# PAC_MiP_POV_v18_10_18_17_new_02.net
KiCad netlist of a schematic drawn in EAGLE
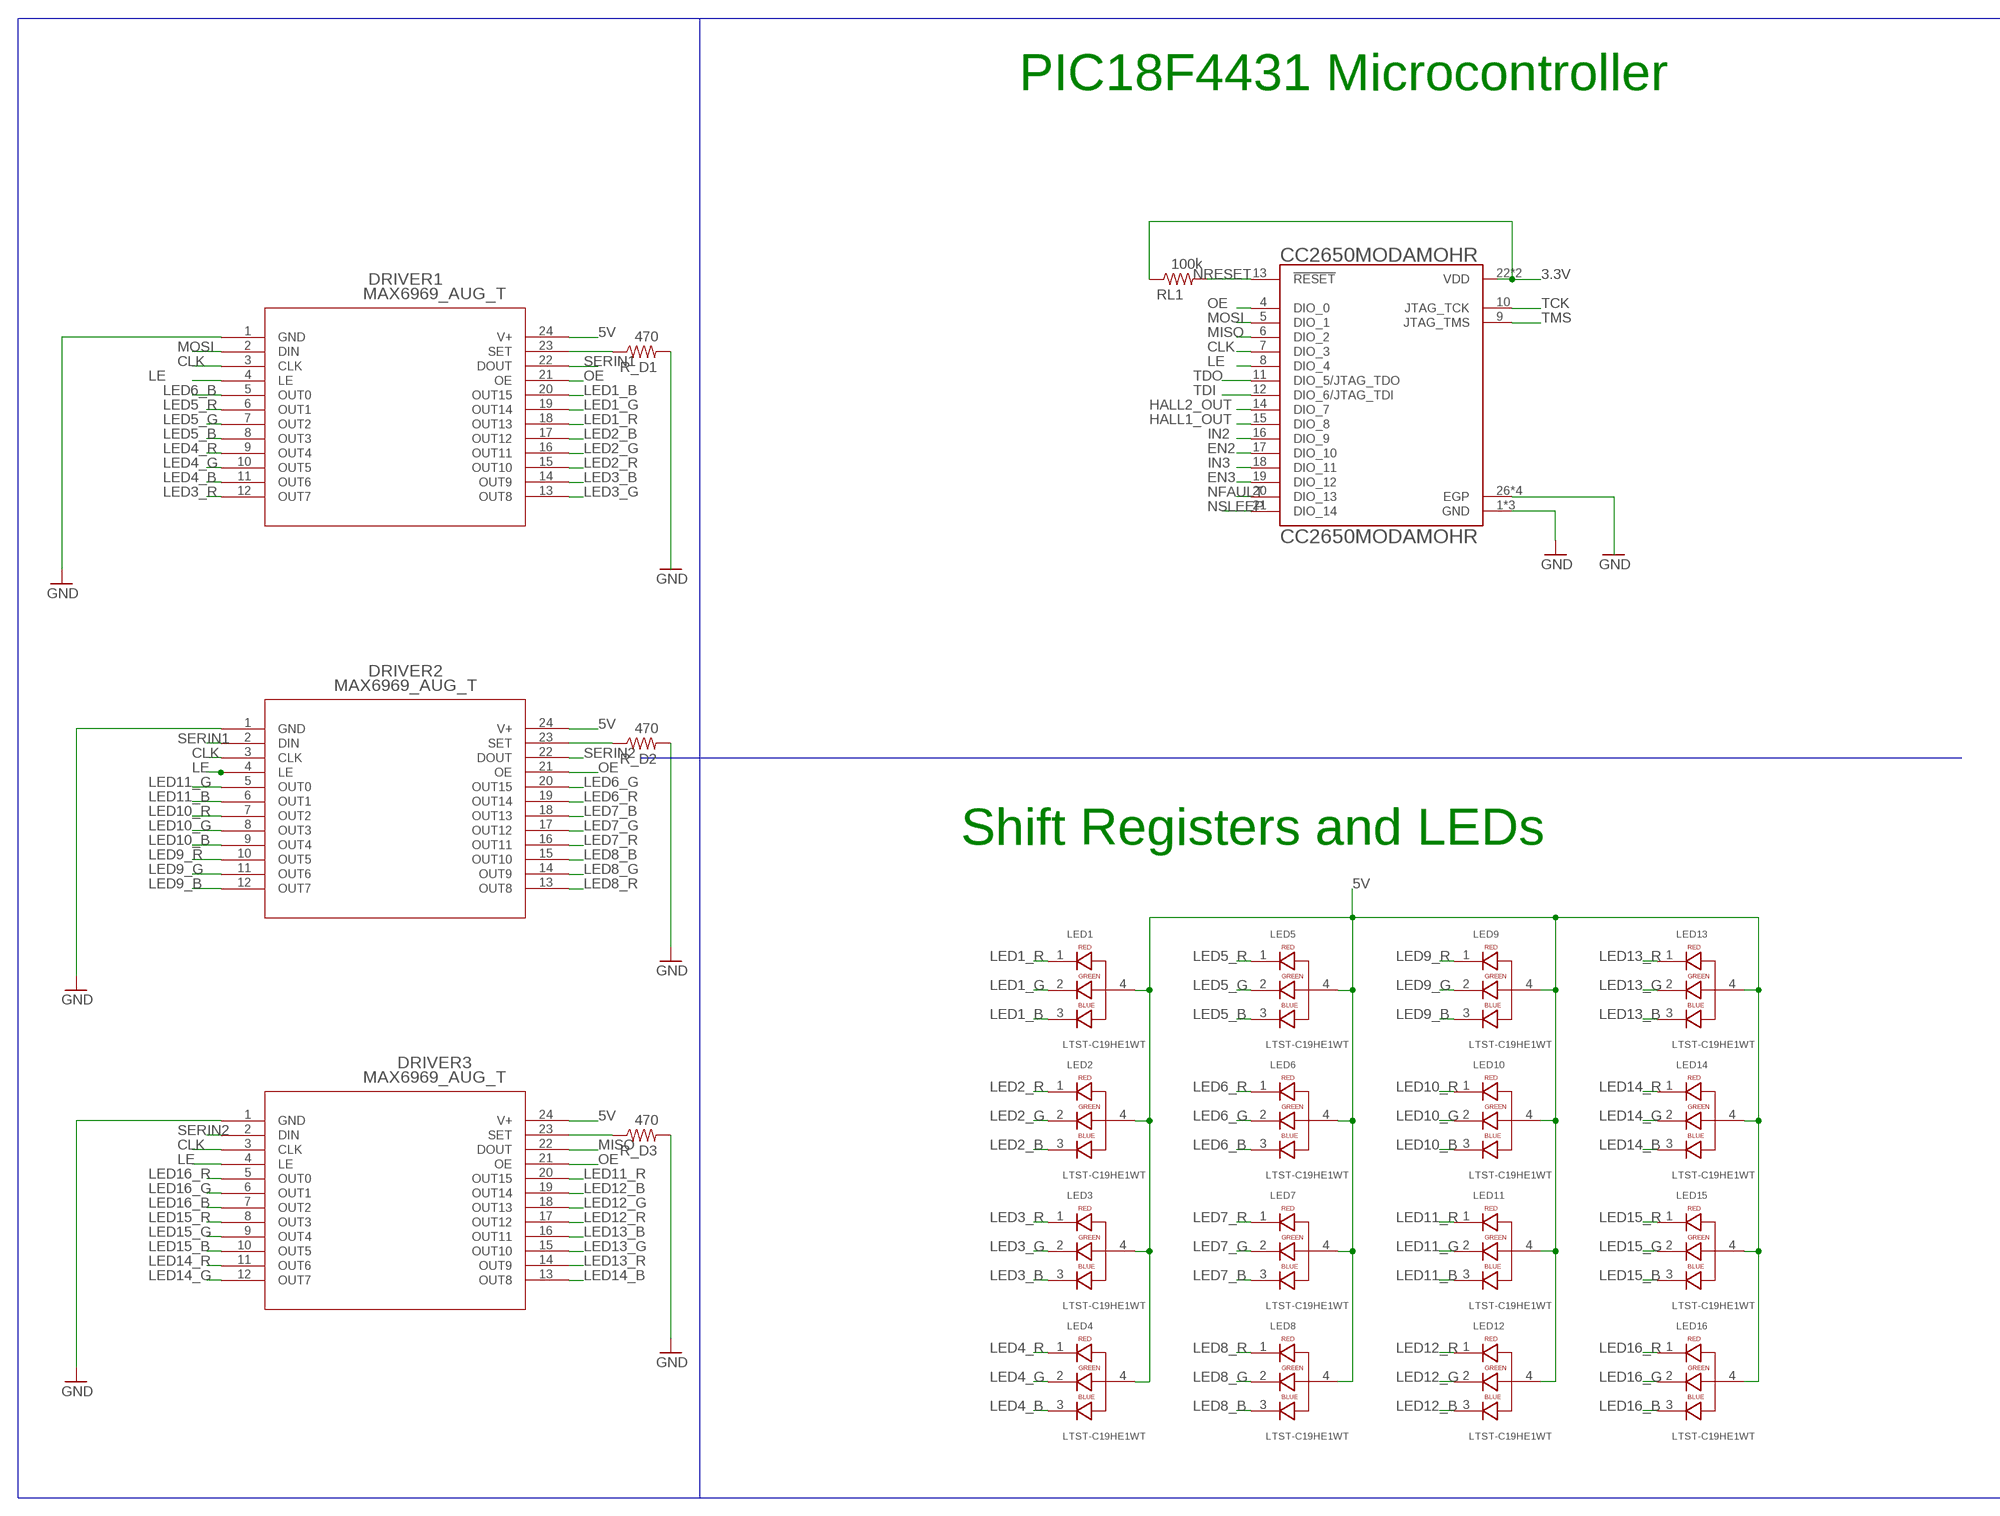
[diagram p0: schematic, sheet 1, part 1 of 2]
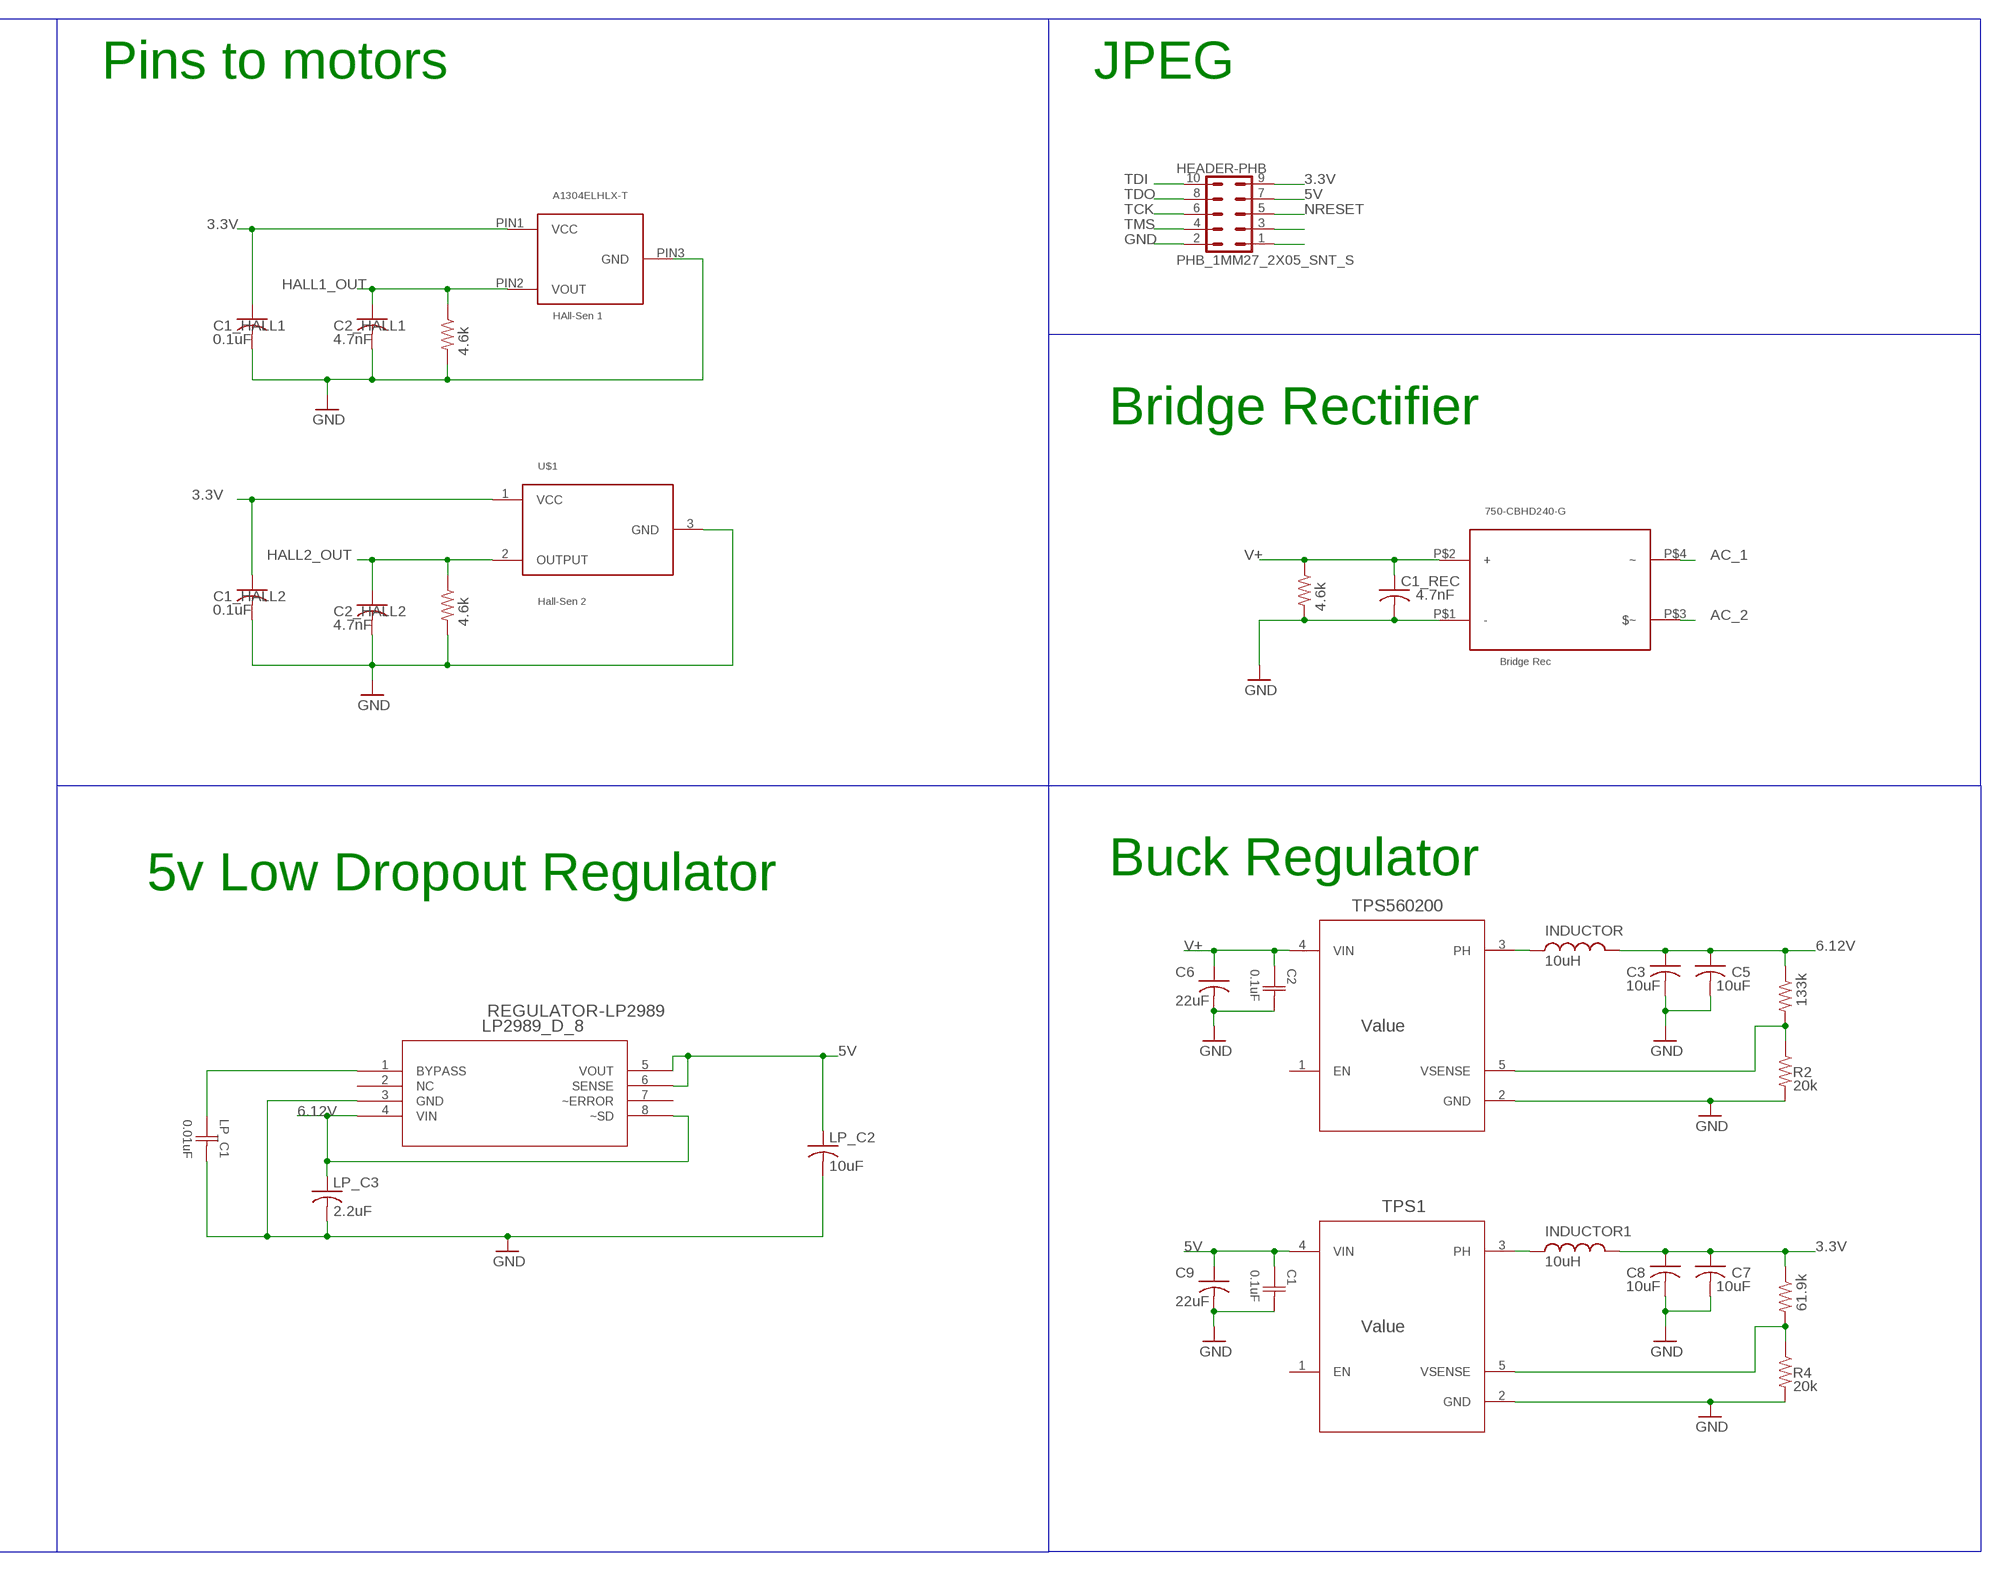
[diagram p1: schematic, sheet 1, part 2 of 2]

(export (version "E")
  (design (tool "Eeschema 10.0.6"))
  (components
    (comp (ref "750-CBHD240-G")
      (value "Bridge Rec")
      (footprint "eagle-import:750-CDBHD240-G")
      (libsource (lib "eagle-import") (part "750-CDBHD240-G"))
    )
    (comp (ref "A1304ELHLX-T")
      (value "HAll-Sen 1")
      (footprint "eagle-import:A1304ELHLX-T")
      (libsource (lib "eagle-import") (part "A1304ELHLX-T"))
    )
    (comp (ref "C1")
      (value "0.1uF")
      (footprint "eagle-import:0508")
      (fields
        (field (name "MANUFACTURER_PART_NUMBER") "05083C104MAT2A")
        (field (name "COPYRIGHT") "Copyright (C) 2015 Accelerated Designs. All rights reserved")
      )
      (libsource (lib "eagle-import") (part "05083C104MAT2A"))
    )
    (comp (ref "C1_HALL1")
      (value "0.1uF")
      (footprint "eagle-import:C0805")
      (libsource (lib "eagle-import") (part "C-USC0805"))
    )
    (comp (ref "C1_HALL2")
      (value "0.1uF")
      (footprint "eagle-import:C0805")
      (libsource (lib "eagle-import") (part "C-USC0805"))
    )
    (comp (ref "C1_REC")
      (value "4.7nF")
      (footprint "eagle-import:C0805")
      (libsource (lib "eagle-import") (part "C-USC0805"))
    )
    (comp (ref "C2")
      (value "0.1uF")
      (footprint "eagle-import:0508")
      (fields
        (field (name "MANUFACTURER_PART_NUMBER") "05083C104MAT2A")
        (field (name "COPYRIGHT") "Copyright (C) 2015 Accelerated Designs. All rights reserved")
      )
      (libsource (lib "eagle-import") (part "05083C104MAT2A"))
    )
    (comp (ref "C2_HALL1")
      (value "4.7nF")
      (footprint "eagle-import:C0805")
      (libsource (lib "eagle-import") (part "C-USC0805"))
    )
    (comp (ref "C2_HALL2")
      (value "4.7nF")
      (footprint "eagle-import:C0805")
      (libsource (lib "eagle-import") (part "C-USC0805"))
    )
    (comp (ref "C3")
      (value "10uF")
      (footprint "eagle-import:C0805")
      (libsource (lib "eagle-import") (part "C-USC0805"))
    )
    (comp (ref "C5")
      (value "10uF")
      (footprint "eagle-import:C0805")
      (libsource (lib "eagle-import") (part "C-USC0805"))
    )
    (comp (ref "C6")
      (value "22uF")
      (footprint "eagle-import:C0805")
      (libsource (lib "eagle-import") (part "C-USC0805"))
    )
    (comp (ref "C7")
      (value "10uF")
      (footprint "eagle-import:C0805")
      (libsource (lib "eagle-import") (part "C-USC0805"))
    )
    (comp (ref "C8")
      (value "10uF")
      (footprint "eagle-import:C0805")
      (libsource (lib "eagle-import") (part "C-USC0805"))
    )
    (comp (ref "C9")
      (value "22uF")
      (footprint "eagle-import:C0805")
      (libsource (lib "eagle-import") (part "C-USC0805"))
    )
    (comp (ref "CC2650MODAMOHR")
      (value "CC2650MODAMOHR")
      (footprint "eagle-import:XCVR_CC2650MODAMOHR")
      (fields (field (name "MF") "Texas Instruments"))
      (libsource (lib "eagle-import") (part "CC2650MODAMOHR"))
    )
    (comp (ref "DRIVER1")
      (value "MAX6969_AUG_T")
      (footprint "eagle-import:21_0066J_24")
      (libsource (lib "eagle-import") (part "MAX6969_AUG_T"))
    )
    (comp (ref "DRIVER2")
      (value "MAX6969_AUG_T")
      (footprint "eagle-import:21_0066J_24")
      (libsource (lib "eagle-import") (part "MAX6969_AUG_T"))
    )
    (comp (ref "DRIVER3")
      (value "MAX6969_AUG_T")
      (footprint "eagle-import:21_0066J_24")
      (libsource (lib "eagle-import") (part "MAX6969_AUG_T"))
    )
    (comp (ref "HEADER-PHB")
      (value "PHB_1MM27_2X05_SNT_S")
      (footprint "eagle-import:PHB_1MM27_2X05_SNT")
      (libsource (lib "eagle-import") (part "PHB_1MM27_2X05_?_SSNT"))
    )
    (comp (ref "INDUCTOR")
      (value "10uH")
      (footprint "eagle-import:CDPH4D19FNP100MC")
      (libsource (lib "eagle-import") (part "INDUCTOR-CDPH1D06F"))
    )
    (comp (ref "INDUCTOR1")
      (value "10uH")
      (footprint "eagle-import:CDPH4D19FNP100MC")
      (libsource (lib "eagle-import") (part "INDUCTOR-CDPH1D06F"))
    )
    (comp (ref "LED1")
      (value "LTST-C19HE1WT")
      (footprint "eagle-import:LEDSC85P160X160X35-4N")
      (fields (field (name "MF") "Lite-On"))
      (libsource (lib "eagle-import") (part "LTST-C19HE1WT"))
    )
    (comp (ref "LED2")
      (value "LTST-C19HE1WT")
      (footprint "eagle-import:LEDSC85P160X160X35-4N")
      (fields (field (name "MF") "Lite-On"))
      (libsource (lib "eagle-import") (part "LTST-C19HE1WT"))
    )
    (comp (ref "LED3")
      (value "LTST-C19HE1WT")
      (footprint "eagle-import:LEDSC85P160X160X35-4N")
      (fields (field (name "MF") "Lite-On"))
      (libsource (lib "eagle-import") (part "LTST-C19HE1WT"))
    )
    (comp (ref "LED4")
      (value "LTST-C19HE1WT")
      (footprint "eagle-import:LEDSC85P160X160X35-4N")
      (fields (field (name "MF") "Lite-On"))
      (libsource (lib "eagle-import") (part "LTST-C19HE1WT"))
    )
    (comp (ref "LED5")
      (value "LTST-C19HE1WT")
      (footprint "eagle-import:LEDSC85P160X160X35-4N")
      (fields (field (name "MF") "Lite-On"))
      (libsource (lib "eagle-import") (part "LTST-C19HE1WT"))
    )
    (comp (ref "LED6")
      (value "LTST-C19HE1WT")
      (footprint "eagle-import:LEDSC85P160X160X35-4N")
      (fields (field (name "MF") "Lite-On"))
      (libsource (lib "eagle-import") (part "LTST-C19HE1WT"))
    )
    (comp (ref "LED7")
      (value "LTST-C19HE1WT")
      (footprint "eagle-import:LEDSC85P160X160X35-4N")
      (fields (field (name "MF") "Lite-On"))
      (libsource (lib "eagle-import") (part "LTST-C19HE1WT"))
    )
    (comp (ref "LED8")
      (value "LTST-C19HE1WT")
      (footprint "eagle-import:LEDSC85P160X160X35-4N")
      (fields (field (name "MF") "Lite-On"))
      (libsource (lib "eagle-import") (part "LTST-C19HE1WT"))
    )
    (comp (ref "LED9")
      (value "LTST-C19HE1WT")
      (footprint "eagle-import:LEDSC85P160X160X35-4N")
      (fields (field (name "MF") "Lite-On"))
      (libsource (lib "eagle-import") (part "LTST-C19HE1WT"))
    )
    (comp (ref "LED10")
      (value "LTST-C19HE1WT")
      (footprint "eagle-import:LEDSC85P160X160X35-4N")
      (fields (field (name "MF") "Lite-On"))
      (libsource (lib "eagle-import") (part "LTST-C19HE1WT"))
    )
    (comp (ref "LED11")
      (value "LTST-C19HE1WT")
      (footprint "eagle-import:LEDSC85P160X160X35-4N")
      (fields (field (name "MF") "Lite-On"))
      (libsource (lib "eagle-import") (part "LTST-C19HE1WT"))
    )
    (comp (ref "LED12")
      (value "LTST-C19HE1WT")
      (footprint "eagle-import:LEDSC85P160X160X35-4N")
      (fields (field (name "MF") "Lite-On"))
      (libsource (lib "eagle-import") (part "LTST-C19HE1WT"))
    )
    (comp (ref "LED13")
      (value "LTST-C19HE1WT")
      (footprint "eagle-import:LEDSC85P160X160X35-4N")
      (fields (field (name "MF") "Lite-On"))
      (libsource (lib "eagle-import") (part "LTST-C19HE1WT"))
    )
    (comp (ref "LED14")
      (value "LTST-C19HE1WT")
      (footprint "eagle-import:LEDSC85P160X160X35-4N")
      (fields (field (name "MF") "Lite-On"))
      (libsource (lib "eagle-import") (part "LTST-C19HE1WT"))
    )
    (comp (ref "LED15")
      (value "LTST-C19HE1WT")
      (footprint "eagle-import:LEDSC85P160X160X35-4N")
      (fields (field (name "MF") "Lite-On"))
      (libsource (lib "eagle-import") (part "LTST-C19HE1WT"))
    )
    (comp (ref "LED16")
      (value "LTST-C19HE1WT")
      (footprint "eagle-import:LEDSC85P160X160X35-4N")
      (fields (field (name "MF") "Lite-On"))
      (libsource (lib "eagle-import") (part "LTST-C19HE1WT"))
    )
    (comp (ref "LP_C1")
      (value "0.01uF")
      (footprint "eagle-import:LLL18")
      (fields
        (field (name "MANUFACTURER_PART_NUMBER") "LLL185R71E103MA01L")
        (field (name "COPYRIGHT") "Copyright (C) 2015 Accelerated Designs. All rights reserved")
      )
      (libsource (lib "eagle-import") (part "LLL185R71E103MA01L"))
    )
    (comp (ref "LP_C2")
      (value "10uF")
      (footprint "eagle-import:C0805")
      (libsource (lib "eagle-import") (part "C-USC0805"))
    )
    (comp (ref "LP_C3")
      (value "2.2uF")
      (footprint "eagle-import:C0805")
      (libsource (lib "eagle-import") (part "C-USC0805"))
    )
    (comp (ref "R1")
      (value "133k")
      (footprint "eagle-import:R0805")
      (libsource (lib "eagle-import") (part "R-US_R0805"))
    )
    (comp (ref "R1_HALL")
      (value "4.6k")
      (footprint "eagle-import:R0805")
      (libsource (lib "eagle-import") (part "R-US_R0805"))
    )
    (comp (ref "R1_HALL2")
      (value "4.6k")
      (footprint "eagle-import:R0805")
      (libsource (lib "eagle-import") (part "R-US_R0805"))
    )
    (comp (ref "R1_REC")
      (value "4.6k")
      (footprint "eagle-import:R0805")
      (libsource (lib "eagle-import") (part "R-US_R0805"))
    )
    (comp (ref "R2")
      (value "20k")
      (footprint "eagle-import:R0805")
      (libsource (lib "eagle-import") (part "R-US_R0805"))
    )
    (comp (ref "R3")
      (value "61.9k")
      (footprint "eagle-import:R0805")
      (libsource (lib "eagle-import") (part "R-US_R0805"))
    )
    (comp (ref "R4")
      (value "20k")
      (footprint "eagle-import:R0805")
      (libsource (lib "eagle-import") (part "R-US_R0805"))
    )
    (comp (ref "REGULATOR-LP2989")
      (value "LP2989_D_8")
      (footprint "eagle-import:M08A")
      (fields
        (field (name "PARTNUMBER") "LP2989AIM-18")
        (field (name "BASE_PN") "LP2989")
        (field (name "COMP") "TypeLDO")
        (field (name "LIBRARY") "ReferenceLP2989AIM")
        (field (name "PARTNUMBER_1") "LP2989AIM-18")
        (field (name "PIN") "Count8")
        (field (name "SYMBOL") "NameLP2989AIM-18")
        (field (name "TYPE") "LP2989AIM-1.8")
        (field (name "VENDOR") "NationalSemiconductor")
        (field (name "VERSION") "1")
      )
      (libsource (lib "eagle-import") (part "LP2989_D_8"))
    )
    (comp (ref "RL1")
      (value "100k")
      (footprint "eagle-import:R0805")
      (libsource (lib "eagle-import") (part "resistor_R-US_R0805"))
    )
    (comp (ref "R_D1")
      (value "470")
      (footprint "eagle-import:R0805")
      (libsource (lib "eagle-import") (part "resistor_R-US_R0805"))
    )
    (comp (ref "R_D2")
      (value "470")
      (footprint "eagle-import:R0805")
      (libsource (lib "eagle-import") (part "resistor_R-US_R0805"))
    )
    (comp (ref "R_D3")
      (value "470")
      (footprint "eagle-import:R0805")
      (libsource (lib "eagle-import") (part "resistor_R-US_R0805"))
    )
    (comp (ref "TPS1")
      (value "Value")
      (footprint "eagle-import:DBV0005A_N")
      (fields (field (name "MANUFACTURER") "Texas Instruments") (field (name "PARTNUMBER") "TPS560200DBV"))
      (libsource (lib "eagle-import") (part "TPS560200DBVR"))
    )
    (comp (ref "TPS560200")
      (value "Value")
      (footprint "eagle-import:DBV0005A_N")
      (fields (field (name "MANUFACTURER") "Texas Instruments") (field (name "PARTNUMBER") "TPS560200DBV"))
      (libsource (lib "eagle-import") (part "TPS560200DBVR"))
    )
    (comp (ref "U$1")
      (value "Hall-Sen 2")
      (footprint "eagle-import:SOT-23-3")
      (libsource (lib "eagle-import") (part "SS39ET"))
    )
  )
  (nets
    (net (code "2") (name "/3.3V") (class "Default")
      (node (ref "A1304ELHLX-T") (pin "PIN1") (pinfunction "VCC_PIN1") (pintype "bidirectional"))
      (node (ref "C1_HALL1") (pin "1") (pinfunction "1_1") (pintype "passive"))
      (node (ref "C1_HALL2") (pin "1") (pinfunction "1_1") (pintype "passive"))
      (node (ref "C7") (pin "1") (pinfunction "1_1") (pintype "passive"))
      (node (ref "C8") (pin "1") (pinfunction "1_1") (pintype "passive"))
      (node (ref "CC2650MODAMOHR") (pin "22") (pinfunction "VDD_22") (pintype "power_in"))
      (node (ref "CC2650MODAMOHR") (pin "23") (pinfunction "VDD_23") (pintype "power_in"))
      (node (ref "HEADER-PHB") (pin "9") (pinfunction "9_9") (pintype "passive"))
      (node (ref "INDUCTOR1") (pin "P$2") (pinfunction "P$2_P$2") (pintype "bidirectional"))
      (node (ref "R3") (pin "1") (pinfunction "1_1") (pintype "passive"))
      (node (ref "RL1") (pin "1") (pinfunction "1_1") (pintype "passive"))
      (node (ref "U$1") (pin "1") (pinfunction "VCC_1") (pintype "bidirectional"))
    )
    (net (code "3") (name "/5V") (class "Default")
      (node (ref "C1") (pin "1") (pinfunction "1_1") (pintype "passive"))
      (node (ref "C9") (pin "1") (pinfunction "1_1") (pintype "passive"))
      (node (ref "DRIVER1") (pin "24") (pinfunction "V+_24") (pintype "power_in"))
      (node (ref "DRIVER2") (pin "24") (pinfunction "V+_24") (pintype "power_in"))
      (node (ref "DRIVER3") (pin "24") (pinfunction "V+_24") (pintype "power_in"))
      (node (ref "HEADER-PHB") (pin "7") (pinfunction "7_7") (pintype "passive"))
      (node (ref "LED1") (pin "4") (pinfunction "4_4") (pintype "passive"))
      (node (ref "LED10") (pin "4") (pinfunction "4_4") (pintype "passive"))
      (node (ref "LED11") (pin "4") (pinfunction "4_4") (pintype "passive"))
      (node (ref "LED12") (pin "4") (pinfunction "4_4") (pintype "passive"))
      (node (ref "LED13") (pin "4") (pinfunction "4_4") (pintype "passive"))
      (node (ref "LED14") (pin "4") (pinfunction "4_4") (pintype "passive"))
      (node (ref "LED15") (pin "4") (pinfunction "4_4") (pintype "passive"))
      (node (ref "LED16") (pin "4") (pinfunction "4_4") (pintype "passive"))
      (node (ref "LED2") (pin "4") (pinfunction "4_4") (pintype "passive"))
      (node (ref "LED3") (pin "4") (pinfunction "4_4") (pintype "passive"))
      (node (ref "LED4") (pin "4") (pinfunction "4_4") (pintype "passive"))
      (node (ref "LED5") (pin "4") (pinfunction "4_4") (pintype "passive"))
      (node (ref "LED6") (pin "4") (pinfunction "4_4") (pintype "passive"))
      (node (ref "LED7") (pin "4") (pinfunction "4_4") (pintype "passive"))
      (node (ref "LED8") (pin "4") (pinfunction "4_4") (pintype "passive"))
      (node (ref "LED9") (pin "4") (pinfunction "4_4") (pintype "passive"))
      (node (ref "LP_C2") (pin "1") (pinfunction "1_1") (pintype "passive"))
      (node (ref "REGULATOR-LP2989") (pin "5") (pinfunction "VOUT_5") (pintype "output"))
      (node (ref "REGULATOR-LP2989") (pin "6") (pinfunction "SENSE_6") (pintype "passive"))
      (node (ref "TPS1") (pin "4") (pinfunction "VIN_4") (pintype "power_in"))
    )
    (net (code "4") (name "/6.12V") (class "Default")
      (node (ref "C3") (pin "1") (pinfunction "1_1") (pintype "passive"))
      (node (ref "C5") (pin "1") (pinfunction "1_1") (pintype "passive"))
      (node (ref "INDUCTOR") (pin "P$2") (pinfunction "P$2_P$2") (pintype "bidirectional"))
      (node (ref "LP_C3") (pin "1") (pinfunction "1_1") (pintype "passive"))
      (node (ref "R1") (pin "1") (pinfunction "1_1") (pintype "passive"))
      (node (ref "REGULATOR-LP2989") (pin "4") (pinfunction "VIN_4") (pintype "input"))
      (node (ref "REGULATOR-LP2989") (pin "8") (pinfunction "~{SD}_8") (pintype "passive"))
    )
    (net (code "5") (name "/AC_1") (class "Default")
      (node (ref "750-CBHD240-G") (pin "P$4") (pinfunction "~_P$4") (pintype "bidirectional"))
    )
    (net (code "6") (name "/AC_2") (class "Default")
      (node (ref "750-CBHD240-G") (pin "P$3") (pinfunction "$~{}_P$3") (pintype "bidirectional"))
    )
    (net (code "7") (name "/CLK") (class "Default")
      (node (ref "CC2650MODAMOHR") (pin "7") (pinfunction "DIO_3_7") (pintype "bidirectional"))
      (node (ref "DRIVER1") (pin "3") (pinfunction "CLK_3") (pintype "input"))
      (node (ref "DRIVER2") (pin "3") (pinfunction "CLK_3") (pintype "input"))
      (node (ref "DRIVER3") (pin "3") (pinfunction "CLK_3") (pintype "input"))
    )
    (net (code "8") (name "/EN2") (class "Default")
      (node (ref "CC2650MODAMOHR") (pin "17") (pinfunction "DIO_10_17") (pintype "bidirectional"))
    )
    (net (code "9") (name "/EN3") (class "Default")
      (node (ref "CC2650MODAMOHR") (pin "19") (pinfunction "DIO_12_19") (pintype "bidirectional"))
    )
    (net (code "10") (name "/HALL1_OUT") (class "Default")
      (node (ref "A1304ELHLX-T") (pin "PIN2") (pinfunction "VOUT_PIN2") (pintype "bidirectional"))
      (node (ref "C2_HALL1") (pin "1") (pinfunction "1_1") (pintype "passive"))
      (node (ref "CC2650MODAMOHR") (pin "15") (pinfunction "DIO_8_15") (pintype "bidirectional"))
      (node (ref "R1_HALL") (pin "1") (pinfunction "1_1") (pintype "passive"))
    )
    (net (code "11") (name "/HALL2_OUT") (class "Default")
      (node (ref "C2_HALL2") (pin "1") (pinfunction "1_1") (pintype "passive"))
      (node (ref "CC2650MODAMOHR") (pin "14") (pinfunction "DIO_7_14") (pintype "bidirectional"))
      (node (ref "R1_HALL2") (pin "1") (pinfunction "1_1") (pintype "passive"))
      (node (ref "U$1") (pin "2") (pinfunction "OUTPUT_2") (pintype "bidirectional"))
    )
    (net (code "12") (name "/IN2") (class "Default")
      (node (ref "CC2650MODAMOHR") (pin "16") (pinfunction "DIO_9_16") (pintype "bidirectional"))
    )
    (net (code "13") (name "/IN3") (class "Default")
      (node (ref "CC2650MODAMOHR") (pin "18") (pinfunction "DIO_11_18") (pintype "bidirectional"))
    )
    (net (code "14") (name "/LE") (class "Default")
      (node (ref "CC2650MODAMOHR") (pin "8") (pinfunction "DIO_4_8") (pintype "bidirectional"))
      (node (ref "DRIVER1") (pin "4") (pinfunction "LE_4") (pintype "input"))
      (node (ref "DRIVER2") (pin "4") (pinfunction "LE_4") (pintype "input"))
      (node (ref "DRIVER3") (pin "4") (pinfunction "LE_4") (pintype "input"))
    )
    (net (code "15") (name "/LED1_B") (class "Default")
      (node (ref "DRIVER1") (pin "20") (pinfunction "OUT15_20") (pintype "output"))
      (node (ref "LED1") (pin "3") (pinfunction "3_3") (pintype "passive"))
    )
    (net (code "16") (name "/LED1_G") (class "Default")
      (node (ref "DRIVER1") (pin "19") (pinfunction "OUT14_19") (pintype "output"))
      (node (ref "LED1") (pin "2") (pinfunction "2_2") (pintype "passive"))
    )
    (net (code "17") (name "/LED1_R") (class "Default")
      (node (ref "DRIVER1") (pin "18") (pinfunction "OUT13_18") (pintype "output"))
      (node (ref "LED1") (pin "1") (pinfunction "1_1") (pintype "passive"))
    )
    (net (code "18") (name "/LED2_B") (class "Default")
      (node (ref "DRIVER1") (pin "17") (pinfunction "OUT12_17") (pintype "output"))
      (node (ref "LED2") (pin "3") (pinfunction "3_3") (pintype "passive"))
    )
    (net (code "19") (name "/LED2_G") (class "Default")
      (node (ref "DRIVER1") (pin "16") (pinfunction "OUT11_16") (pintype "output"))
      (node (ref "LED2") (pin "2") (pinfunction "2_2") (pintype "passive"))
    )
    (net (code "20") (name "/LED2_R") (class "Default")
      (node (ref "DRIVER1") (pin "15") (pinfunction "OUT10_15") (pintype "output"))
      (node (ref "LED2") (pin "1") (pinfunction "1_1") (pintype "passive"))
    )
    (net (code "21") (name "/LED3_B") (class "Default")
      (node (ref "DRIVER1") (pin "14") (pinfunction "OUT9_14") (pintype "output"))
      (node (ref "LED3") (pin "3") (pinfunction "3_3") (pintype "passive"))
    )
    (net (code "22") (name "/LED3_G") (class "Default")
      (node (ref "DRIVER1") (pin "13") (pinfunction "OUT8_13") (pintype "output"))
      (node (ref "LED3") (pin "2") (pinfunction "2_2") (pintype "passive"))
    )
    (net (code "23") (name "/LED3_R") (class "Default")
      (node (ref "DRIVER1") (pin "12") (pinfunction "OUT7_12") (pintype "output"))
      (node (ref "LED3") (pin "1") (pinfunction "1_1") (pintype "passive"))
    )
    (net (code "24") (name "/LED4_B") (class "Default")
      (node (ref "DRIVER1") (pin "11") (pinfunction "OUT6_11") (pintype "output"))
      (node (ref "LED4") (pin "3") (pinfunction "3_3") (pintype "passive"))
    )
    (net (code "25") (name "/LED4_G") (class "Default")
      (node (ref "DRIVER1") (pin "10") (pinfunction "OUT5_10") (pintype "output"))
      (node (ref "LED4") (pin "2") (pinfunction "2_2") (pintype "passive"))
    )
    (net (code "26") (name "/LED4_R") (class "Default")
      (node (ref "DRIVER1") (pin "9") (pinfunction "OUT4_9") (pintype "output"))
      (node (ref "LED4") (pin "1") (pinfunction "1_1") (pintype "passive"))
    )
    (net (code "27") (name "/LED5_B") (class "Default")
      (node (ref "DRIVER1") (pin "8") (pinfunction "OUT3_8") (pintype "output"))
      (node (ref "LED5") (pin "3") (pinfunction "3_3") (pintype "passive"))
    )
    (net (code "28") (name "/LED5_G") (class "Default")
      (node (ref "DRIVER1") (pin "7") (pinfunction "OUT2_7") (pintype "output"))
      (node (ref "LED5") (pin "2") (pinfunction "2_2") (pintype "passive"))
    )
    (net (code "29") (name "/LED5_R") (class "Default")
      (node (ref "DRIVER1") (pin "6") (pinfunction "OUT1_6") (pintype "output"))
      (node (ref "LED5") (pin "1") (pinfunction "1_1") (pintype "passive"))
    )
    (net (code "30") (name "/LED6_B") (class "Default")
      (node (ref "DRIVER1") (pin "5") (pinfunction "OUT0_5") (pintype "output"))
      (node (ref "LED6") (pin "3") (pinfunction "3_3") (pintype "passive"))
    )
    (net (code "31") (name "/LED6_G") (class "Default")
      (node (ref "DRIVER2") (pin "20") (pinfunction "OUT15_20") (pintype "output"))
      (node (ref "LED6") (pin "2") (pinfunction "2_2") (pintype "passive"))
    )
    (net (code "32") (name "/LED6_R") (class "Default")
      (node (ref "DRIVER2") (pin "19") (pinfunction "OUT14_19") (pintype "output"))
      (node (ref "LED6") (pin "1") (pinfunction "1_1") (pintype "passive"))
    )
    (net (code "33") (name "/LED7_B") (class "Default")
      (node (ref "DRIVER2") (pin "18") (pinfunction "OUT13_18") (pintype "output"))
      (node (ref "LED7") (pin "3") (pinfunction "3_3") (pintype "passive"))
    )
    (net (code "34") (name "/LED7_G") (class "Default")
      (node (ref "DRIVER2") (pin "17") (pinfunction "OUT12_17") (pintype "output"))
      (node (ref "LED7") (pin "2") (pinfunction "2_2") (pintype "passive"))
    )
    (net (code "35") (name "/LED7_R") (class "Default")
      (node (ref "DRIVER2") (pin "16") (pinfunction "OUT11_16") (pintype "output"))
      (node (ref "LED7") (pin "1") (pinfunction "1_1") (pintype "passive"))
    )
    (net (code "36") (name "/LED8_B") (class "Default")
      (node (ref "DRIVER2") (pin "15") (pinfunction "OUT10_15") (pintype "output"))
      (node (ref "LED8") (pin "3") (pinfunction "3_3") (pintype "passive"))
    )
    (net (code "37") (name "/LED8_G") (class "Default")
      (node (ref "DRIVER2") (pin "14") (pinfunction "OUT9_14") (pintype "output"))
      (node (ref "LED8") (pin "2") (pinfunction "2_2") (pintype "passive"))
    )
    (net (code "38") (name "/LED8_R") (class "Default")
      (node (ref "DRIVER2") (pin "13") (pinfunction "OUT8_13") (pintype "output"))
      (node (ref "LED8") (pin "1") (pinfunction "1_1") (pintype "passive"))
    )
    (net (code "39") (name "/LED9_B") (class "Default")
      (node (ref "DRIVER2") (pin "12") (pinfunction "OUT7_12") (pintype "output"))
      (node (ref "LED9") (pin "3") (pinfunction "3_3") (pintype "passive"))
    )
    (net (code "40") (name "/LED9_G") (class "Default")
      (node (ref "DRIVER2") (pin "11") (pinfunction "OUT6_11") (pintype "output"))
      (node (ref "LED9") (pin "2") (pinfunction "2_2") (pintype "passive"))
    )
    (net (code "41") (name "/LED9_R") (class "Default")
      (node (ref "DRIVER2") (pin "10") (pinfunction "OUT5_10") (pintype "output"))
      (node (ref "LED9") (pin "1") (pinfunction "1_1") (pintype "passive"))
    )
    (net (code "42") (name "/LED10_B") (class "Default")
      (node (ref "DRIVER2") (pin "9") (pinfunction "OUT4_9") (pintype "output"))
      (node (ref "LED10") (pin "3") (pinfunction "3_3") (pintype "passive"))
    )
    (net (code "43") (name "/LED10_G") (class "Default")
      (node (ref "DRIVER2") (pin "8") (pinfunction "OUT3_8") (pintype "output"))
      (node (ref "LED10") (pin "2") (pinfunction "2_2") (pintype "passive"))
    )
    (net (code "44") (name "/LED10_R") (class "Default")
      (node (ref "DRIVER2") (pin "7") (pinfunction "OUT2_7") (pintype "output"))
      (node (ref "LED10") (pin "1") (pinfunction "1_1") (pintype "passive"))
    )
    (net (code "45") (name "/LED11_B") (class "Default")
      (node (ref "DRIVER2") (pin "6") (pinfunction "OUT1_6") (pintype "output"))
      (node (ref "LED11") (pin "3") (pinfunction "3_3") (pintype "passive"))
    )
    (net (code "46") (name "/LED11_G") (class "Default")
      (node (ref "DRIVER2") (pin "5") (pinfunction "OUT0_5") (pintype "output"))
      (node (ref "LED11") (pin "2") (pinfunction "2_2") (pintype "passive"))
    )
    (net (code "47") (name "/LED11_R") (class "Default")
      (node (ref "DRIVER3") (pin "20") (pinfunction "OUT15_20") (pintype "output"))
      (node (ref "LED11") (pin "1") (pinfunction "1_1") (pintype "passive"))
    )
    (net (code "48") (name "/LED12_B") (class "Default")
      (node (ref "DRIVER3") (pin "19") (pinfunction "OUT14_19") (pintype "output"))
      (node (ref "LED12") (pin "3") (pinfunction "3_3") (pintype "passive"))
    )
    (net (code "49") (name "/LED12_G") (class "Default")
      (node (ref "DRIVER3") (pin "18") (pinfunction "OUT13_18") (pintype "output"))
      (node (ref "LED12") (pin "2") (pinfunction "2_2") (pintype "passive"))
    )
    (net (code "50") (name "/LED12_R") (class "Default")
      (node (ref "DRIVER3") (pin "17") (pinfunction "OUT12_17") (pintype "output"))
      (node (ref "LED12") (pin "1") (pinfunction "1_1") (pintype "passive"))
    )
    (net (code "51") (name "/LED13_B") (class "Default")
      (node (ref "DRIVER3") (pin "16") (pinfunction "OUT11_16") (pintype "output"))
      (node (ref "LED13") (pin "3") (pinfunction "3_3") (pintype "passive"))
    )
    (net (code "52") (name "/LED13_G") (class "Default")
      (node (ref "DRIVER3") (pin "15") (pinfunction "OUT10_15") (pintype "output"))
      (node (ref "LED13") (pin "2") (pinfunction "2_2") (pintype "passive"))
    )
    (net (code "53") (name "/LED13_R") (class "Default")
      (node (ref "DRIVER3") (pin "14") (pinfunction "OUT9_14") (pintype "output"))
      (node (ref "LED13") (pin "1") (pinfunction "1_1") (pintype "passive"))
    )
    (net (code "54") (name "/LED14_B") (class "Default")
      (node (ref "DRIVER3") (pin "13") (pinfunction "OUT8_13") (pintype "output"))
      (node (ref "LED14") (pin "3") (pinfunction "3_3") (pintype "passive"))
    )
    (net (code "55") (name "/LED14_G") (class "Default")
      (node (ref "DRIVER3") (pin "12") (pinfunction "OUT7_12") (pintype "output"))
      (node (ref "LED14") (pin "2") (pinfunction "2_2") (pintype "passive"))
    )
    (net (code "56") (name "/LED14_R") (class "Default")
      (node (ref "DRIVER3") (pin "11") (pinfunction "OUT6_11") (pintype "output"))
      (node (ref "LED14") (pin "1") (pinfunction "1_1") (pintype "passive"))
    )
    (net (code "57") (name "/LED15_B") (class "Default")
      (node (ref "DRIVER3") (pin "10") (pinfunction "OUT5_10") (pintype "output"))
      (node (ref "LED15") (pin "3") (pinfunction "3_3") (pintype "passive"))
    )
    (net (code "58") (name "/LED15_G") (class "Default")
      (node (ref "DRIVER3") (pin "9") (pinfunction "OUT4_9") (pintype "output"))
      (node (ref "LED15") (pin "2") (pinfunction "2_2") (pintype "passive"))
    )
    (net (code "59") (name "/LED15_R") (class "Default")
      (node (ref "DRIVER3") (pin "8") (pinfunction "OUT3_8") (pintype "output"))
      (node (ref "LED15") (pin "1") (pinfunction "1_1") (pintype "passive"))
    )
    (net (code "60") (name "/LED16_B") (class "Default")
      (node (ref "DRIVER3") (pin "7") (pinfunction "OUT2_7") (pintype "output"))
      (node (ref "LED16") (pin "3") (pinfunction "3_3") (pintype "passive"))
    )
    (net (code "61") (name "/LED16_G") (class "Default")
      (node (ref "DRIVER3") (pin "6") (pinfunction "OUT1_6") (pintype "output"))
      (node (ref "LED16") (pin "2") (pinfunction "2_2") (pintype "passive"))
    )
    (net (code "62") (name "/LED16_R") (class "Default")
      (node (ref "DRIVER3") (pin "5") (pinfunction "OUT0_5") (pintype "output"))
      (node (ref "LED16") (pin "1") (pinfunction "1_1") (pintype "passive"))
    )
    (net (code "63") (name "/MISO") (class "Default")
      (node (ref "CC2650MODAMOHR") (pin "6") (pinfunction "DIO_2_6") (pintype "bidirectional"))
      (node (ref "DRIVER3") (pin "22") (pinfunction "DOUT_22") (pintype "input"))
    )
    (net (code "64") (name "/MOSI") (class "Default")
      (node (ref "CC2650MODAMOHR") (pin "5") (pinfunction "DIO_1_5") (pintype "bidirectional"))
      (node (ref "DRIVER1") (pin "2") (pinfunction "DIN_2") (pintype "input"))
    )
    (net (code "65") (name "/NFAULT") (class "Default")
      (node (ref "CC2650MODAMOHR") (pin "20") (pinfunction "DIO_13_20") (pintype "bidirectional"))
    )
    (net (code "66") (name "/NRESET") (class "Default")
      (node (ref "CC2650MODAMOHR") (pin "13") (pinfunction "~{RESET}_13") (pintype "input"))
      (node (ref "HEADER-PHB") (pin "5") (pinfunction "5_5") (pintype "passive"))
      (node (ref "RL1") (pin "2") (pinfunction "2_2") (pintype "passive"))
    )
    (net (code "67") (name "/NSLEEP") (class "Default")
      (node (ref "CC2650MODAMOHR") (pin "21") (pinfunction "DIO_14_21") (pintype "bidirectional"))
    )
    (net (code "68") (name "/OE") (class "Default")
      (node (ref "CC2650MODAMOHR") (pin "4") (pinfunction "DIO_0_4") (pintype "bidirectional"))
      (node (ref "DRIVER1") (pin "21") (pinfunction "OE_21") (pintype "output"))
      (node (ref "DRIVER2") (pin "21") (pinfunction "OE_21") (pintype "output"))
      (node (ref "DRIVER3") (pin "21") (pinfunction "OE_21") (pintype "output"))
    )
    (net (code "69") (name "/SERIN1") (class "Default")
      (node (ref "DRIVER1") (pin "22") (pinfunction "DOUT_22") (pintype "input"))
      (node (ref "DRIVER2") (pin "2") (pinfunction "DIN_2") (pintype "input"))
    )
    (net (code "70") (name "/SERIN2") (class "Default")
      (node (ref "DRIVER2") (pin "22") (pinfunction "DOUT_22") (pintype "input"))
      (node (ref "DRIVER3") (pin "2") (pinfunction "DIN_2") (pintype "input"))
    )
    (net (code "71") (name "/TCK") (class "Default")
      (node (ref "CC2650MODAMOHR") (pin "10") (pinfunction "JTAG_TCK_10") (pintype "bidirectional"))
      (node (ref "HEADER-PHB") (pin "6") (pinfunction "6_6") (pintype "passive"))
    )
    (net (code "72") (name "/TDI") (class "Default")
      (node (ref "CC2650MODAMOHR") (pin "12") (pinfunction "DIO_6/JTAG_TDI_12") (pintype "bidirectional"))
      (node (ref "HEADER-PHB") (pin "10") (pinfunction "10_10") (pintype "passive"))
    )
    (net (code "73") (name "/TDO") (class "Default")
      (node (ref "CC2650MODAMOHR") (pin "11") (pinfunction "DIO_5/JTAG_TDO_11") (pintype "bidirectional"))
      (node (ref "HEADER-PHB") (pin "8") (pinfunction "8_8") (pintype "passive"))
    )
    (net (code "74") (name "/TMS") (class "Default")
      (node (ref "CC2650MODAMOHR") (pin "9") (pinfunction "JTAG_TMS_9") (pintype "bidirectional"))
      (node (ref "HEADER-PHB") (pin "4") (pinfunction "4_4") (pintype "passive"))
    )
    (net (code "75") (name "/V+") (class "Default")
      (node (ref "750-CBHD240-G") (pin "P$2") (pinfunction "+_P$2") (pintype "bidirectional"))
      (node (ref "C1_REC") (pin "1") (pinfunction "1_1") (pintype "passive"))
      (node (ref "C2") (pin "1") (pinfunction "1_1") (pintype "passive"))
      (node (ref "C6") (pin "1") (pinfunction "1_1") (pintype "passive"))
      (node (ref "R1_REC") (pin "1") (pinfunction "1_1") (pintype "passive"))
      (node (ref "TPS560200") (pin "4") (pinfunction "VIN_4") (pintype "power_in"))
    )
    (net (code "77") (name "GND") (class "Default")
      (node (ref "750-CBHD240-G") (pin "P$1") (pinfunction "-_P$1") (pintype "bidirectional"))
      (node (ref "A1304ELHLX-T") (pin "PIN3") (pinfunction "GND_PIN3") (pintype "bidirectional"))
      (node (ref "C1") (pin "2") (pinfunction "2_2") (pintype "passive"))
      (node (ref "C1_HALL1") (pin "2") (pinfunction "2_2") (pintype "passive"))
      (node (ref "C1_HALL2") (pin "2") (pinfunction "2_2") (pintype "passive"))
      (node (ref "C1_REC") (pin "2") (pinfunction "2_2") (pintype "passive"))
      (node (ref "C2") (pin "2") (pinfunction "2_2") (pintype "passive"))
      (node (ref "C2_HALL1") (pin "2") (pinfunction "2_2") (pintype "passive"))
      (node (ref "C2_HALL2") (pin "2") (pinfunction "2_2") (pintype "passive"))
      (node (ref "C3") (pin "2") (pinfunction "2_2") (pintype "passive"))
      (node (ref "C5") (pin "2") (pinfunction "2_2") (pintype "passive"))
      (node (ref "C6") (pin "2") (pinfunction "2_2") (pintype "passive"))
      (node (ref "C7") (pin "2") (pinfunction "2_2") (pintype "passive"))
      (node (ref "C8") (pin "2") (pinfunction "2_2") (pintype "passive"))
      (node (ref "C9") (pin "2") (pinfunction "2_2") (pintype "passive"))
      (node (ref "CC2650MODAMOHR") (pin "1") (pinfunction "GND_1") (pintype "power_in"))
      (node (ref "CC2650MODAMOHR") (pin "25") (pinfunction "GND_25") (pintype "power_in"))
      (node (ref "CC2650MODAMOHR") (pin "26") (pinfunction "EGP_26") (pintype "power_in"))
      (node (ref "CC2650MODAMOHR") (pin "27") (pinfunction "EGP_27") (pintype "power_in"))
      (node (ref "CC2650MODAMOHR") (pin "28") (pinfunction "EGP_28") (pintype "power_in"))
      (node (ref "CC2650MODAMOHR") (pin "29") (pinfunction "EGP_29") (pintype "power_in"))
      (node (ref "CC2650MODAMOHR") (pin "3") (pinfunction "GND_3") (pintype "power_in"))
      (node (ref "DRIVER1") (pin "1") (pinfunction "GND_1") (pintype "power_in"))
      (node (ref "DRIVER2") (pin "1") (pinfunction "GND_1") (pintype "power_in"))
      (node (ref "DRIVER3") (pin "1") (pinfunction "GND_1") (pintype "power_in"))
      (node (ref "HEADER-PHB") (pin "2") (pinfunction "2_2") (pintype "passive"))
      (node (ref "LP_C1") (pin "2") (pinfunction "2_2") (pintype "passive"))
      (node (ref "LP_C2") (pin "2") (pinfunction "2_2") (pintype "passive"))
      (node (ref "LP_C3") (pin "2") (pinfunction "2_2") (pintype "passive"))
      (node (ref "R1_HALL") (pin "2") (pinfunction "2_2") (pintype "passive"))
      (node (ref "R1_HALL2") (pin "2") (pinfunction "2_2") (pintype "passive"))
      (node (ref "R1_REC") (pin "2") (pinfunction "2_2") (pintype "passive"))
      (node (ref "R2") (pin "2") (pinfunction "2_2") (pintype "passive"))
      (node (ref "R4") (pin "2") (pinfunction "2_2") (pintype "passive"))
      (node (ref "REGULATOR-LP2989") (pin "3") (pinfunction "GND_3") (pintype "passive"))
      (node (ref "R_D2") (pin "2") (pinfunction "2_2") (pintype "passive"))
      (node (ref "R_D3") (pin "2") (pinfunction "2_2") (pintype "passive"))
      (node (ref "TPS1") (pin "2") (pinfunction "GND_2") (pintype "power_in"))
      (node (ref "TPS560200") (pin "2") (pinfunction "GND_2") (pintype "power_in"))
      (node (ref "U$1") (pin "3") (pinfunction "GND_3") (pintype "bidirectional"))
    )
    (net (code "78") (name "Net-(DRIVER1-SET)") (class "Default")
      (node (ref "DRIVER1") (pin "23") (pinfunction "SET_23") (pintype "passive"))
      (node (ref "R_D1") (pin "1") (pinfunction "1_1") (pintype "passive"))
    )
    (net (code "79") (name "Net-(DRIVER2-SET)") (class "Default")
      (node (ref "DRIVER2") (pin "23") (pinfunction "SET_23") (pintype "passive"))
      (node (ref "R_D2") (pin "1") (pinfunction "1_1") (pintype "passive"))
    )
    (net (code "80") (name "Net-(DRIVER3-SET)") (class "Default")
      (node (ref "DRIVER3") (pin "23") (pinfunction "SET_23") (pintype "passive"))
      (node (ref "R_D3") (pin "1") (pinfunction "1_1") (pintype "passive"))
    )
    (net (code "81") (name "Net-(REGULATOR-LP2989-BYPASS)") (class "Default")
      (node (ref "LP_C1") (pin "1") (pinfunction "1_1") (pintype "passive"))
      (node (ref "REGULATOR-LP2989") (pin "1") (pinfunction "BYPASS_1") (pintype "passive"))
    )
    (net (code "82") (name "Net-(TPS1-PH)") (class "Default")
      (node (ref "INDUCTOR1") (pin "P$1") (pinfunction "P$1_P$1") (pintype "bidirectional"))
      (node (ref "TPS1") (pin "3") (pinfunction "PH_3") (pintype "power_in"))
    )
    (net (code "83") (name "Net-(TPS1-VSENSE)") (class "Default")
      (node (ref "R3") (pin "2") (pinfunction "2_2") (pintype "passive"))
      (node (ref "R4") (pin "1") (pinfunction "1_1") (pintype "passive"))
      (node (ref "TPS1") (pin "5") (pinfunction "VSENSE_5") (pintype "input"))
    )
    (net (code "84") (name "Net-(TPS560200-PH)") (class "Default")
      (node (ref "INDUCTOR") (pin "P$1") (pinfunction "P$1_P$1") (pintype "bidirectional"))
      (node (ref "TPS560200") (pin "3") (pinfunction "PH_3") (pintype "power_in"))
    )
    (net (code "85") (name "Net-(TPS560200-VSENSE)") (class "Default")
      (node (ref "R1") (pin "2") (pinfunction "2_2") (pintype "passive"))
      (node (ref "R2") (pin "1") (pinfunction "1_1") (pintype "passive"))
      (node (ref "TPS560200") (pin "5") (pinfunction "VSENSE_5") (pintype "input"))
    )
    (net (code "86") (name "unconnected-(HEADER-PHB-Pad1)") (class "Default")
      (node (ref "HEADER-PHB") (pin "1") (pinfunction "1_1") (pintype "passive"))
    )
    (net (code "87") (name "unconnected-(HEADER-PHB-Pad3)") (class "Default")
      (node (ref "HEADER-PHB") (pin "3") (pinfunction "3_3") (pintype "passive"))
    )
    (net (code "88") (name "unconnected-(REGULATOR-LP2989-NC-Pad2)") (class "Default")
      (node (ref "REGULATOR-LP2989") (pin "2") (pinfunction "NC_2") (pintype "passive"))
    )
    (net (code "89") (name "unconnected-(REGULATOR-LP2989-~{ERROR}-Pad7)") (class "Default")
      (node (ref "REGULATOR-LP2989") (pin "7") (pinfunction "~{ERROR}_7") (pintype "passive"))
    )
    (net (code "90") (name "unconnected-(R_D1-Pad2)") (class "Default")
      (node (ref "R_D1") (pin "2") (pinfunction "2_2") (pintype "passive"))
    )
    (net (code "91") (name "unconnected-(TPS1-EN-Pad1)") (class "Default")
      (node (ref "TPS1") (pin "1") (pinfunction "EN_1") (pintype "input"))
    )
    (net (code "92") (name "unconnected-(TPS560200-EN-Pad1)") (class "Default")
      (node (ref "TPS560200") (pin "1") (pinfunction "EN_1") (pintype "input"))
    )
  )
)
